# GC-Sch.net
KiCad netlist of a schematic drawn in Altium Designer
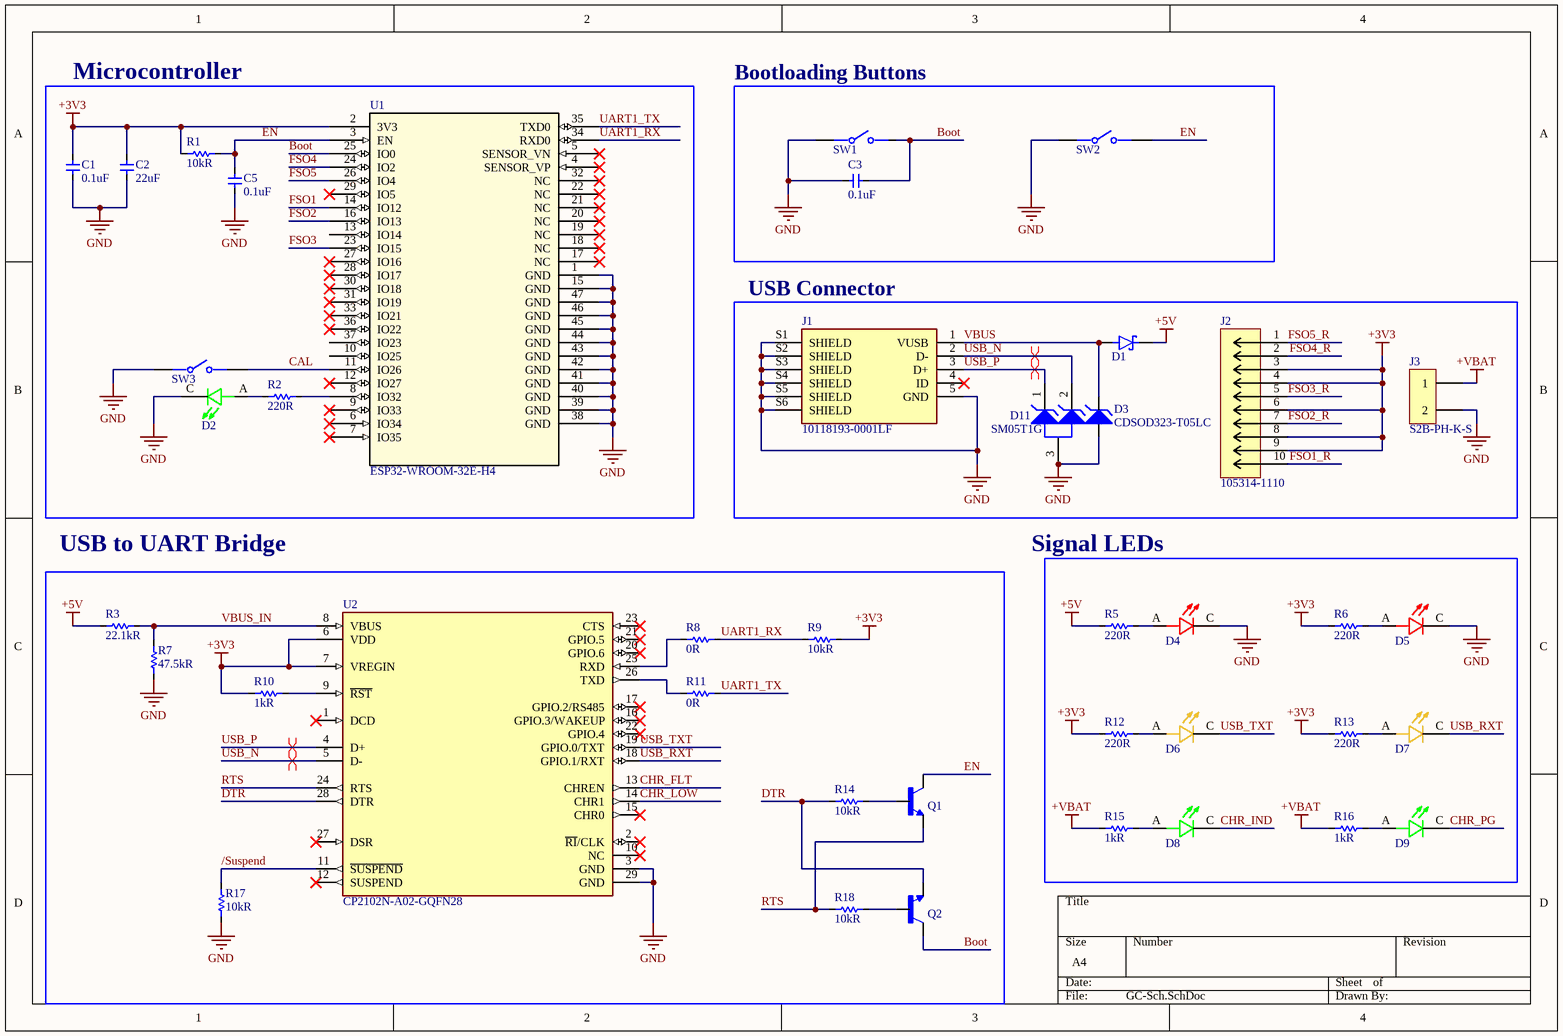
[diagram p0: GC-Sch.SchDoc]

(export (version "E")
  (design (tool "Eeschema 10.0.6"))
  (components
    (comp (ref "C1")
      (value "CL10B104JB8NNNC")
      (footprint "0603")
      (fields (field (name "MANUFACTURER") "Samsung") (field (name "CAPACITANCE") "0.1uF"))
      (libsource (lib "GC-Schlib1") (part "CL10B104JB8NNNC"))
    )
    (comp (ref "C2")
      (value "CL10A226MP8NUNE")
      (footprint "0603")
      (fields (field (name "MANUFACTURER") "Samsung") (field (name "CAPACITANCE") "22uF"))
      (libsource (lib "GC-Schlib1") (part "CL10A226MP8NUNE"))
    )
    (comp (ref "C3")
      (value "CL10B104JB8NNNC")
      (footprint "0603")
      (fields (field (name "MANUFACTURER") "Samsung") (field (name "CAPACITANCE") "0.1uF"))
      (libsource (lib "GC-Schlib1") (part "C-CL10B104JB8NNNC"))
    )
    (comp (ref "C5")
      (value "CL10B104JB8NNNC")
      (footprint "0603")
      (fields (field (name "MANUFACTURER") "Samsung") (field (name "CAPACITANCE") "0.1uF"))
      (libsource (lib "GC-Schlib1") (part "CL10B104JB8NNNC"))
    )
    (comp (ref "D1")
      (value "D-BAT760-7")
      (footprint "SOD2513X120N")
      (description "Rectifier Diode, Schottky, 1 Phase, 1 Element, 1A, 30V V(RRM), Silicon")
      (fields (field (name "MANUFACTURER") "Diodes") (field (name "MANUFACTURER PART NUMBER") "BAT760-7"))
      (libsource (lib "GC-Schlib1") (part "D-BAT760-7"))
    )
    (comp (ref "D2")
      (value "SML-D12P8WT86")
      (footprint "D-SML-D12U1WT86")
      (description "Single Color LED, Pure Green, Diffused Milky White, 1.2mm")
      (fields (field (name "MANUFACTURER") "Rohm"))
      (libsource (lib "GC-Schlib1") (part "D-SML-D12P8WT86"))
    )
    (comp (ref "D3")
      (value "CDSOD323-T05LC")
      (footprint "SOD2513X120N")
      (description "Trans Voltage Suppressor Diode, 250W, 5V V(RWM), Bidirectional, 2 Element, Silicon")
      (fields (field (name "MANUFACTURER") "Bourns"))
      (libsource (lib "GC-Schlib1") (part "D-CDSOD323-T05LC"))
    )
    (comp (ref "D4")
      (value "SML-D12U1WT86")
      (footprint "D-SML-D12U1WT86")
      (description "Single Color LED, Red, Milky White, 1.2mm")
      (fields (field (name "MANUFACTURER") "Rohm"))
      (libsource (lib "GC-Schlib1") (part "D-SML-D12U1WT86"))
    )
    (comp (ref "D5")
      (value "SML-D12U1WT86")
      (footprint "D-SML-D12U1WT86")
      (description "Single Color LED, Red, Milky White, 1.2mm")
      (fields (field (name "MANUFACTURER") "Rohm"))
      (libsource (lib "GC-Schlib1") (part "D-SML-D12U1WT86"))
    )
    (comp (ref "D6")
      (value "SML-D12Y1WT86")
      (footprint "D-SML-D12U1WT86")
      (description "Single Color LED, Yellow, Milky White, 1.2mm")
      (fields (field (name "MANUFACTURER") "Rohm"))
      (libsource (lib "GC-Schlib1") (part "D-SML-D12Y1WT86"))
    )
    (comp (ref "D7")
      (value "SML-D12Y1WT86")
      (footprint "D-SML-D12U1WT86")
      (description "Single Color LED, Yellow, Milky White, 1.2mm")
      (fields (field (name "MANUFACTURER") "Rohm"))
      (libsource (lib "GC-Schlib1") (part "D-SML-D12Y1WT86"))
    )
    (comp (ref "D8")
      (value "SML-D12P8WT86")
      (footprint "D-SML-D12U1WT86")
      (description "Single Color LED, Pure Green, Diffused Milky White, 1.2mm")
      (fields (field (name "MANUFACTURER") "Rohm"))
      (libsource (lib "GC-Schlib1") (part "D-SML-D12P8WT86"))
    )
    (comp (ref "D9")
      (value "SML-D12P8WT86")
      (footprint "D-SML-D12U1WT86")
      (description "Single Color LED, Pure Green, Diffused Milky White, 1.2mm")
      (fields (field (name "MANUFACTURER") "Rohm"))
      (libsource (lib "GC-Schlib1") (part "D-SML-D12P8WT86"))
    )
    (comp (ref "D11")
      (value "SM05T1G")
      (footprint "ONSC-SOT-23-3-318-08_V")
      (description "Trans Voltage Suppressor Diode, 300W, 5V V(RWM), Unidirectional, 2 Element, Silicon, TO-236AB")
      (fields (field (name "MANUFACTURER") "ON Semiconductor"))
      (libsource (lib "GC-Schlib1") (part "D-SM05T1G"))
    )
    (comp (ref "J1")
      (value "10118193-0001LF")
      (footprint "AMPHENOL_10118193-0001LF")
      (description "FCI Right Angle Surface Mount Mount Female USB Connector; 100 V ac; 1.8A")
      (fields (field (name "MANUFACTURER") "Amphenol ICC / FCI"))
      (libsource (lib "GC-Schlib1") (part "J-10118193-0001LF"))
    )
    (comp (ref "J2")
      (value "105314-1110")
      (footprint "temp")
      (description "Rectangular Power Connector, 10 Contact(s), Male, Solder Terminal")
      (fields (field (name "MANUFACTURER") "Molex"))
      (libsource (lib "GC-Schlib1") (part "J-105314-1110"))
    )
    (comp (ref "J3")
      (value "S2B-PH-K-S")
      (footprint "JST_S2B-PH-K-S(LF)(SN)")
      (description "Header for PCB; pitch 2.00mm; 2-contacts; THT; male; side entry; 100V/2A")
      (fields
        (field (name "MANUFACTURER") "JST")
        (field (name "MANUFACTURER PART NUMBER") "S2B-PH-K-S(LF)(SN)")
      )
      (libsource (lib "GC-Schlib1") (part "J-S2B-PH-K-S(LF)(SN)"))
    )
    (comp (ref "Q1")
      (value "SS8050-G")
      (footprint "TRANS_SS8050-G")
      (description "Small Signal Bipolar Transistor, 1.5A I(C), 25V V(BR)CEO, 1-Element, NPN, Silicon")
      (fields (field (name "MANUFACTURER") "Comchip"))
      (libsource (lib "") (part "Q-SS8050-G_1"))
    )
    (comp (ref "Q2")
      (value "SS8050-G")
      (footprint "TRANS_SS8050-G")
      (description "Small Signal Bipolar Transistor, 1.5A I(C), 25V V(BR)CEO, 1-Element, NPN, Silicon")
      (fields (field (name "MANUFACTURER") "Comchip"))
      (libsource (lib "GC-Schlib1") (part "Q-SS8050-G"))
    )
    (comp (ref "R1")
      (value "AC0603FR-1310KL")
      (footprint "0603 - R")
      (fields
        (field (name "MANUFACTURER") "Yageo")
        (field (name "TOLERANCE") "1%")
        (field (name "RESISTANCE") "10kR")
      )
      (libsource (lib "GC-Schlib1") (part "AC0603FR-1310KL"))
    )
    (comp (ref "R2")
      (value "R-RMCF0603JT220R")
      (footprint "0603 - R")
      (fields
        (field (name "MANUFACTURER") "Stackpole Electronics")
        (field (name "MANUFACTURER PART NUMBER") "RMCF0603JT220R")
        (field (name "TOLERANCE") "5%")
        (field (name "RESISTANCE") "220R")
      )
      (libsource (lib "GC-Schlib1") (part "R-RMCF0603JT220R"))
    )
    (comp (ref "R3")
      (value "RMCF0603FT22K1")
      (footprint "0603 - R")
      (fields
        (field (name "MANUFACTURER") "Stackpole Electronics")
        (field (name "TOLERANCE") "1%")
        (field (name "RESISTANCE") "22.1kR")
      )
      (libsource (lib "GC-Schlib1") (part "R-RMCF0603FT22K1"))
    )
    (comp (ref "R5")
      (value "R-RMCF0603JT220R")
      (footprint "0603 - R")
      (fields
        (field (name "MANUFACTURER") "Stackpole Electronics")
        (field (name "MANUFACTURER PART NUMBER") "RMCF0603JT220R")
        (field (name "TOLERANCE") "5%")
        (field (name "RESISTANCE") "220R")
      )
      (libsource (lib "GC-Schlib1") (part "R-RMCF0603JT220R"))
    )
    (comp (ref "R6")
      (value "R-RMCF0603JT220R")
      (footprint "0603 - R")
      (fields
        (field (name "MANUFACTURER") "Stackpole Electronics")
        (field (name "MANUFACTURER PART NUMBER") "RMCF0603JT220R")
        (field (name "TOLERANCE") "5%")
        (field (name "RESISTANCE") "220R")
      )
      (libsource (lib "GC-Schlib1") (part "R-RMCF0603JT220R"))
    )
    (comp (ref "R7")
      (value "RC0402FR-0747K5L")
      (footprint "0603 - R")
      (fields
        (field (name "MANUFACTURER") "Yageo")
        (field (name "TOLERANCE") "1%")
        (field (name "RESISTANCE") "47.5kR")
      )
      (libsource (lib "GC-Schlib1") (part "R-RC0402FR-0747K5L"))
    )
    (comp (ref "R8")
      (value "ERJ-3GEY0R00V")
      (footprint "0603 - R")
      (description "Fixed Resistor, Metal Glaze/thick Film, 0.1W, 0ohm, Surface Mount, 0603")
      (fields (field (name "MANUFACTURER") "Panasonic") (field (name "RESISTANCE") "0R"))
      (libsource (lib "GC-Schlib1") (part "R-ERJ-3GEY0R00V"))
    )
    (comp (ref "R9")
      (value "AC0603FR-1310KL")
      (footprint "0603 - R")
      (fields
        (field (name "MANUFACTURER") "Yageo")
        (field (name "TOLERANCE") "1%")
        (field (name "RESISTANCE") "10kR")
      )
      (libsource (lib "GC-Schlib1") (part "R-AC0603FR-1310KL"))
    )
    (comp (ref "R10")
      (value "RC0603FR-071KL")
      (footprint "0603 - R")
      (fields
        (field (name "MANUFACTURER") "Yageo")
        (field (name "TOLERANCE") "1%")
        (field (name "RESISTANCE") "1kR")
      )
      (libsource (lib "GC-Schlib1") (part "R-RC0603FR-071KL"))
    )
    (comp (ref "R11")
      (value "ERJ-3GEY0R00V")
      (footprint "0603 - R")
      (description "Fixed Resistor, Metal Glaze/thick Film, 0.1W, 0ohm, Surface Mount, 0603")
      (fields (field (name "MANUFACTURER") "Panasonic") (field (name "RESISTANCE") "0R"))
      (libsource (lib "GC-Schlib1") (part "R-ERJ-3GEY0R00V"))
    )
    (comp (ref "R12")
      (value "R-RMCF0603JT220R")
      (footprint "0603 - R")
      (fields
        (field (name "MANUFACTURER") "Stackpole Electronics")
        (field (name "MANUFACTURER PART NUMBER") "RMCF0603JT220R")
        (field (name "TOLERANCE") "5%")
        (field (name "RESISTANCE") "220R")
      )
      (libsource (lib "GC-Schlib1") (part "R-RMCF0603JT220R"))
    )
    (comp (ref "R13")
      (value "R-RMCF0603JT220R")
      (footprint "0603 - R")
      (fields
        (field (name "MANUFACTURER") "Stackpole Electronics")
        (field (name "MANUFACTURER PART NUMBER") "RMCF0603JT220R")
        (field (name "TOLERANCE") "5%")
        (field (name "RESISTANCE") "220R")
      )
      (libsource (lib "GC-Schlib1") (part "R-RMCF0603JT220R"))
    )
    (comp (ref "R14")
      (value "AC0603FR-1310KL")
      (footprint "0603 - R")
      (fields
        (field (name "MANUFACTURER") "Yageo")
        (field (name "TOLERANCE") "1%")
        (field (name "RESISTANCE") "10kR")
      )
      (libsource (lib "GC-Schlib1") (part "R-AC0603FR-1310KL"))
    )
    (comp (ref "R15")
      (value "RC0603FR-071KL")
      (footprint "0603 - R")
      (fields
        (field (name "MANUFACTURER") "Yageo")
        (field (name "TOLERANCE") "1%")
        (field (name "RESISTANCE") "1kR")
      )
      (libsource (lib "GC-Schlib1") (part "R-RC0603FR-071KL"))
    )
    (comp (ref "R16")
      (value "RC0603FR-071KL")
      (footprint "0603 - R")
      (fields
        (field (name "MANUFACTURER") "Yageo")
        (field (name "TOLERANCE") "1%")
        (field (name "RESISTANCE") "1kR")
      )
      (libsource (lib "GC-Schlib1") (part "R-RC0603FR-071KL"))
    )
    (comp (ref "R17")
      (value "AC0603FR-1310KL")
      (footprint "0603 - R")
      (fields
        (field (name "MANUFACTURER") "Yageo")
        (field (name "TOLERANCE") "1%")
        (field (name "RESISTANCE") "10kR")
      )
      (libsource (lib "GC-Schlib1") (part "R-AC0603FR-1310KL"))
    )
    (comp (ref "R18")
      (value "AC0603FR-1310KL")
      (footprint "0603 - R")
      (fields
        (field (name "MANUFACTURER") "Yageo")
        (field (name "TOLERANCE") "1%")
        (field (name "RESISTANCE") "10kR")
      )
      (libsource (lib "GC-Schlib1") (part "R-AC0603FR-1310KL"))
    )
    (comp (ref "SW1")
      (value "SW-61300211121")
      (footprint "2 Pin Through Hole - Pitch 2.54 mm")
      (fields
        (field (name "MANUFACTURER") "Wurth Electronics")
        (field (name "MANUFACTURER PART NUMBER") "61300211121")
      )
      (libsource (lib "GC-Schlib1") (part "SW-61300211121"))
    )
    (comp (ref "SW2")
      (value "SW-61300211121")
      (footprint "2 Pin Through Hole - Pitch 2.54 mm")
      (fields
        (field (name "MANUFACTURER") "Wurth Electronics")
        (field (name "MANUFACTURER PART NUMBER") "61300211121")
      )
      (libsource (lib "GC-Schlib1") (part "SW-61300211121"))
    )
    (comp (ref "SW3")
      (value "SW-61300211121")
      (footprint "2 Pin Through Hole - Pitch 2.54 mm")
      (fields
        (field (name "MANUFACTURER") "Wurth Electronics")
        (field (name "MANUFACTURER PART NUMBER") "61300211121")
      )
      (libsource (lib "GC-Schlib1") (part "SW-61300211121"))
    )
    (comp (ref "U1")
      (value "ESP32-WROOM-32E-H4")
      (footprint "ESP32­WROOM­32E_EXP")
      (description "Rx Txrx Mod Wifi Trace Ant SMD")
      (fields (field (name "MANUFACTURER") "Espressif Systems"))
      (libsource (lib "GC-Schlib1") (part "ESP32-WROOM-32E-H4"))
    )
    (comp (ref "U2")
      (value "CP2102N-A02-GQFN28")
      (footprint "FP-CP2102N-A02-GQFN28-IPC_A")
      (description "USB Bus Controller, CMOS")
      (fields (field (name "MANUFACTURER") "Silicon Labs"))
      (libsource (lib "GC-Schlib1") (part "U-CP2102N-A02-GQFN28"))
    )
  )
  (nets
    (net (code "1") (name "+3V3") (class "Default")
      (node (ref "C1") (pin "2") (pinfunction "2_2") (pintype "passive"))
      (node (ref "C2") (pin "1") (pinfunction "1_1") (pintype "passive"))
      (node (ref "J2") (pin "3") (pinfunction "3_3") (pintype "passive"))
      (node (ref "J2") (pin "4") (pinfunction "4_4") (pintype "passive"))
      (node (ref "J2") (pin "6") (pinfunction "6_6") (pintype "passive"))
      (node (ref "J2") (pin "8") (pinfunction "8_8") (pintype "passive"))
      (node (ref "J2") (pin "9") (pinfunction "9_9") (pintype "passive"))
      (node (ref "R1") (pin "1") (pinfunction "1_1") (pintype "passive"))
      (node (ref "R10") (pin "1") (pinfunction "1_1") (pintype "passive"))
      (node (ref "R12") (pin "1") (pinfunction "1_1") (pintype "passive"))
      (node (ref "R13") (pin "1") (pinfunction "1_1") (pintype "passive"))
      (node (ref "R6") (pin "1") (pinfunction "1_1") (pintype "passive"))
      (node (ref "R9") (pin "2") (pinfunction "2_2") (pintype "passive"))
      (node (ref "U1") (pin "2") (pinfunction "3V3_2") (pintype "power_in"))
      (node (ref "U2") (pin "6") (pinfunction "VDD_6") (pintype "power_in"))
      (node (ref "U2") (pin "7") (pinfunction "VREGIN_7") (pintype "input"))
    )
    (net (code "2") (name "+5V") (class "Default")
      (node (ref "D1") (pin "C") (pinfunction "K_C") (pintype "passive"))
      (node (ref "R3") (pin "1") (pinfunction "1_1") (pintype "passive"))
      (node (ref "R5") (pin "1") (pinfunction "1_1") (pintype "passive"))
    )
    (net (code "3") (name "+VBAT") (class "Default")
      (node (ref "J3") (pin "1") (pinfunction "1_1") (pintype "passive"))
      (node (ref "R15") (pin "1") (pinfunction "1_1") (pintype "passive"))
      (node (ref "R16") (pin "1") (pinfunction "1_1") (pintype "passive"))
    )
    (net (code "4") (name "/Boot") (class "Default")
      (node (ref "C3") (pin "1") (pinfunction "1_1") (pintype "passive"))
      (node (ref "Q2") (pin "3") (pinfunction "C_3") (pintype "passive"))
      (node (ref "SW1") (pin "2") (pinfunction "2_2") (pintype "passive"))
      (node (ref "U1") (pin "25") (pinfunction "IO0_25") (pintype "bidirectional"))
    )
    (net (code "5") (name "/CAL") (class "Default")
      (node (ref "SW3") (pin "2") (pinfunction "2_2") (pintype "passive"))
      (node (ref "U1") (pin "11") (pinfunction "IO26_11") (pintype "bidirectional"))
    )
    (net (code "6") (name "/CHR_FLT") (class "Default")
      (node (ref "U2") (pin "13") (pinfunction "CHREN_13") (pintype "output"))
    )
    (net (code "7") (name "/CHR_IND") (class "Default")
      (node (ref "D8") (pin "C") (pinfunction "C_C") (pintype "passive"))
    )
    (net (code "8") (name "/CHR_LOW") (class "Default")
      (node (ref "U2") (pin "14") (pinfunction "CHR1_14") (pintype "output"))
    )
    (net (code "9") (name "/CHR_PG") (class "Default")
      (node (ref "D9") (pin "C") (pinfunction "C_C") (pintype "passive"))
    )
    (net (code "10") (name "/DTR") (class "Default")
      (node (ref "Q2") (pin "2") (pinfunction "E_2") (pintype "passive"))
      (node (ref "R14") (pin "1") (pinfunction "1_1") (pintype "passive"))
      (node (ref "U2") (pin "28") (pinfunction "DTR_28") (pintype "output"))
    )
    (net (code "11") (name "/EN") (class "Default")
      (node (ref "C5") (pin "2") (pinfunction "2_2") (pintype "passive"))
      (node (ref "Q1") (pin "3") (pinfunction "C_3") (pintype "passive"))
      (node (ref "R1") (pin "2") (pinfunction "2_2") (pintype "passive"))
      (node (ref "SW2") (pin "2") (pinfunction "2_2") (pintype "passive"))
      (node (ref "U1") (pin "3") (pinfunction "EN_3") (pintype "input"))
    )
    (net (code "12") (name "/FSO1") (class "Default")
      (node (ref "U1") (pin "14") (pinfunction "IO12_14") (pintype "bidirectional"))
    )
    (net (code "13") (name "/FSO1_R") (class "Default")
      (node (ref "J2") (pin "10") (pinfunction "10_10") (pintype "passive"))
    )
    (net (code "14") (name "/FSO2") (class "Default")
      (node (ref "U1") (pin "16") (pinfunction "IO13_16") (pintype "bidirectional"))
    )
    (net (code "15") (name "/FSO2_R") (class "Default")
      (node (ref "J2") (pin "7") (pinfunction "7_7") (pintype "passive"))
    )
    (net (code "16") (name "/FSO3") (class "Default")
      (node (ref "U1") (pin "23") (pinfunction "IO15_23") (pintype "bidirectional"))
    )
    (net (code "17") (name "/FSO3_R") (class "Default")
      (node (ref "J2") (pin "5") (pinfunction "5_5") (pintype "passive"))
    )
    (net (code "18") (name "/FSO4") (class "Default")
      (node (ref "U1") (pin "24") (pinfunction "IO2_24") (pintype "bidirectional"))
    )
    (net (code "19") (name "/FSO4_R") (class "Default")
      (node (ref "J2") (pin "2") (pinfunction "2_2") (pintype "passive"))
    )
    (net (code "20") (name "/FSO5") (class "Default")
      (node (ref "U1") (pin "26") (pinfunction "IO4_26") (pintype "bidirectional"))
    )
    (net (code "21") (name "/FSO5_R") (class "Default")
      (node (ref "J2") (pin "1") (pinfunction "1_1") (pintype "passive"))
    )
    (net (code "22") (name "/RTS") (class "Default")
      (node (ref "Q1") (pin "2") (pinfunction "E_2") (pintype "passive"))
      (node (ref "R18") (pin "1") (pinfunction "1_1") (pintype "passive"))
      (node (ref "U2") (pin "24") (pinfunction "RTS_24") (pintype "output"))
    )
    (net (code "23") (name "/UART1_RX") (class "Default")
      (node (ref "R8") (pin "2") (pinfunction "2_2") (pintype "passive"))
      (node (ref "R9") (pin "1") (pinfunction "1_1") (pintype "passive"))
      (node (ref "U1") (pin "34") (pinfunction "RXD0_34") (pintype "bidirectional"))
    )
    (net (code "24") (name "/UART1_TX") (class "Default")
      (node (ref "R11") (pin "2") (pinfunction "2_2") (pintype "passive"))
      (node (ref "U1") (pin "35") (pinfunction "TXD0_35") (pintype "bidirectional"))
    )
    (net (code "25") (name "/USB_N") (class "Default")
      (node (ref "D11") (pin "2") (pinfunction "K2_2") (pintype "passive"))
      (node (ref "J1") (pin "2") (pinfunction "D-_2") (pintype "passive"))
      (node (ref "U2") (pin "5") (pinfunction "D-_5") (pintype "passive"))
    )
    (net (code "26") (name "/USB_P") (class "Default")
      (node (ref "D11") (pin "1") (pinfunction "K1_1") (pintype "passive"))
      (node (ref "J1") (pin "3") (pinfunction "D+_3") (pintype "passive"))
      (node (ref "U2") (pin "4") (pinfunction "D+_4") (pintype "passive"))
    )
    (net (code "27") (name "/USB_RXT") (class "Default")
      (node (ref "D7") (pin "C") (pinfunction "C_C") (pintype "passive"))
      (node (ref "U2") (pin "18") (pinfunction "GPIO.1/RXT_18") (pintype "bidirectional"))
    )
    (net (code "28") (name "/USB_TXT") (class "Default")
      (node (ref "D6") (pin "C") (pinfunction "C_C") (pintype "passive"))
      (node (ref "U2") (pin "19") (pinfunction "GPIO.0/TXT_19") (pintype "bidirectional"))
    )
    (net (code "29") (name "/VBUS") (class "Default")
      (node (ref "D1") (pin "A") (pinfunction "A_A") (pintype "passive"))
      (node (ref "D3") (pin "C") (pinfunction "C_C") (pintype "passive"))
      (node (ref "J1") (pin "1") (pinfunction "VUSB_1") (pintype "passive"))
    )
    (net (code "30") (name "/VBUS_IN") (class "Default")
      (node (ref "R3") (pin "2") (pinfunction "2_2") (pintype "passive"))
      (node (ref "R7") (pin "2") (pinfunction "2_2") (pintype "passive"))
      (node (ref "U2") (pin "8") (pinfunction "VBUS_8") (pintype "input"))
    )
    (net (code "31") (name "/{slash}Suspend") (class "Default")
      (node (ref "R17") (pin "2") (pinfunction "2_2") (pintype "passive"))
      (node (ref "U2") (pin "11") (pinfunction "~{SUSPEND}_11") (pintype "output"))
    )
    (net (code "32") (name "GND") (class "Default")
      (node (ref "C1") (pin "1") (pinfunction "1_1") (pintype "passive"))
      (node (ref "C2") (pin "2") (pinfunction "2_2") (pintype "passive"))
      (node (ref "C3") (pin "2") (pinfunction "2_2") (pintype "passive"))
      (node (ref "C5") (pin "1") (pinfunction "1_1") (pintype "passive"))
      (node (ref "D11") (pin "3") (pinfunction "A_3") (pintype "passive"))
      (node (ref "D2") (pin "C") (pinfunction "C_C") (pintype "passive"))
      (node (ref "D3") (pin "A") (pinfunction "A_A") (pintype "passive"))
      (node (ref "D4") (pin "C") (pinfunction "C_C") (pintype "passive"))
      (node (ref "D5") (pin "C") (pinfunction "C_C") (pintype "passive"))
      (node (ref "J1") (pin "5") (pinfunction "GND_5") (pintype "passive"))
      (node (ref "J1") (pin "S1") (pinfunction "SHIELD_S1") (pintype "passive"))
      (node (ref "J1") (pin "S2") (pinfunction "SHIELD_S2") (pintype "passive"))
      (node (ref "J1") (pin "S3") (pinfunction "SHIELD_S3") (pintype "passive"))
      (node (ref "J1") (pin "S4") (pinfunction "SHIELD_S4") (pintype "passive"))
      (node (ref "J1") (pin "S5") (pinfunction "SHIELD_S5") (pintype "passive"))
      (node (ref "J1") (pin "S6") (pinfunction "SHIELD_S6") (pintype "passive"))
      (node (ref "J3") (pin "2") (pinfunction "2_2") (pintype "passive"))
      (node (ref "R17") (pin "1") (pinfunction "1_1") (pintype "passive"))
      (node (ref "R7") (pin "1") (pinfunction "1_1") (pintype "passive"))
      (node (ref "SW1") (pin "1") (pinfunction "1_1") (pintype "passive"))
      (node (ref "SW2") (pin "1") (pinfunction "1_1") (pintype "passive"))
      (node (ref "SW3") (pin "1") (pinfunction "1_1") (pintype "passive"))
      (node (ref "U1") (pin "1") (pinfunction "GND_1") (pintype "power_in"))
      (node (ref "U1") (pin "15") (pinfunction "GND_15") (pintype "power_in"))
      (node (ref "U1") (pin "38") (pinfunction "GND_38") (pintype "power_in"))
      (node (ref "U1") (pin "39") (pinfunction "GND_39") (pintype "power_in"))
      (node (ref "U1") (pin "40") (pinfunction "GND_40") (pintype "power_in"))
      (node (ref "U1") (pin "41") (pinfunction "GND_41") (pintype "power_in"))
      (node (ref "U1") (pin "42") (pinfunction "GND_42") (pintype "power_in"))
      (node (ref "U1") (pin "43") (pinfunction "GND_43") (pintype "power_in"))
      (node (ref "U1") (pin "44") (pinfunction "GND_44") (pintype "power_in"))
      (node (ref "U1") (pin "45") (pinfunction "GND_45") (pintype "power_in"))
      (node (ref "U1") (pin "46") (pinfunction "GND_46") (pintype "power_in"))
      (node (ref "U1") (pin "47") (pinfunction "GND_47") (pintype "power_in"))
      (node (ref "U2") (pin "29") (pinfunction "GND_29") (pintype "power_in"))
      (node (ref "U2") (pin "3") (pinfunction "GND_3") (pintype "power_in"))
    )
    (net (code "33") (name "Net-(D2-PadA)") (class "Default")
      (node (ref "D2") (pin "A") (pinfunction "A_A") (pintype "passive"))
      (node (ref "R2") (pin "2") (pinfunction "2_2") (pintype "passive"))
    )
    (net (code "34") (name "Net-(D4-PadA)") (class "Default")
      (node (ref "D4") (pin "A") (pinfunction "A_A") (pintype "passive"))
      (node (ref "R5") (pin "2") (pinfunction "2_2") (pintype "passive"))
    )
    (net (code "35") (name "Net-(D5-PadA)") (class "Default")
      (node (ref "D5") (pin "A") (pinfunction "A_A") (pintype "passive"))
      (node (ref "R6") (pin "2") (pinfunction "2_2") (pintype "passive"))
    )
    (net (code "36") (name "Net-(D6-PadA)") (class "Default")
      (node (ref "D6") (pin "A") (pinfunction "A_A") (pintype "passive"))
      (node (ref "R12") (pin "2") (pinfunction "2_2") (pintype "passive"))
    )
    (net (code "37") (name "Net-(D7-PadA)") (class "Default")
      (node (ref "D7") (pin "A") (pinfunction "A_A") (pintype "passive"))
      (node (ref "R13") (pin "2") (pinfunction "2_2") (pintype "passive"))
    )
    (net (code "38") (name "Net-(D8-PadA)") (class "Default")
      (node (ref "D8") (pin "A") (pinfunction "A_A") (pintype "passive"))
      (node (ref "R15") (pin "2") (pinfunction "2_2") (pintype "passive"))
    )
    (net (code "39") (name "Net-(D9-PadA)") (class "Default")
      (node (ref "D9") (pin "A") (pinfunction "A_A") (pintype "passive"))
      (node (ref "R16") (pin "2") (pinfunction "2_2") (pintype "passive"))
    )
    (net (code "40") (name "Net-(Q1-B)") (class "Default")
      (node (ref "Q1") (pin "1") (pinfunction "B_1") (pintype "passive"))
      (node (ref "R14") (pin "2") (pinfunction "2_2") (pintype "passive"))
    )
    (net (code "41") (name "Net-(Q2-B)") (class "Default")
      (node (ref "Q2") (pin "1") (pinfunction "B_1") (pintype "passive"))
      (node (ref "R18") (pin "2") (pinfunction "2_2") (pintype "passive"))
    )
    (net (code "42") (name "Net-(U1-IO32)") (class "Default")
      (node (ref "R2") (pin "1") (pinfunction "1_1") (pintype "passive"))
      (node (ref "U1") (pin "8") (pinfunction "IO32_8") (pintype "bidirectional"))
    )
    (net (code "43") (name "Net-(U2-RXD)") (class "Default")
      (node (ref "R8") (pin "1") (pinfunction "1_1") (pintype "passive"))
      (node (ref "U2") (pin "25") (pinfunction "RXD_25") (pintype "input"))
    )
    (net (code "44") (name "Net-(U2-TXD)") (class "Default")
      (node (ref "R11") (pin "1") (pinfunction "1_1") (pintype "passive"))
      (node (ref "U2") (pin "26") (pinfunction "TXD_26") (pintype "output"))
    )
    (net (code "45") (name "Net-(U2-~{RST})") (class "Default")
      (node (ref "R10") (pin "2") (pinfunction "2_2") (pintype "passive"))
      (node (ref "U2") (pin "9") (pinfunction "~{RST}_9") (pintype "input"))
    )
    (net (code "46") (name "unconnected-(J1-ID-Pad4)") (class "Default")
      (node (ref "J1") (pin "4") (pinfunction "ID_4") (pintype "passive+no_connect"))
    )
    (net (code "47") (name "unconnected-(U1-IO5-Pad29)") (class "Default")
      (node (ref "U1") (pin "29") (pinfunction "IO5_29") (pintype "bidirectional+no_connect"))
    )
    (net (code "48") (name "unconnected-(U1-IO14-Pad13)") (class "Default")
      (node (ref "U1") (pin "13") (pinfunction "IO14_13") (pintype "bidirectional"))
    )
    (net (code "49") (name "unconnected-(U1-IO16-Pad27)") (class "Default")
      (node (ref "U1") (pin "27") (pinfunction "IO16_27") (pintype "bidirectional+no_connect"))
    )
    (net (code "50") (name "unconnected-(U1-IO17-Pad28)") (class "Default")
      (node (ref "U1") (pin "28") (pinfunction "IO17_28") (pintype "bidirectional+no_connect"))
    )
    (net (code "51") (name "unconnected-(U1-IO18-Pad30)") (class "Default")
      (node (ref "U1") (pin "30") (pinfunction "IO18_30") (pintype "bidirectional+no_connect"))
    )
    (net (code "52") (name "unconnected-(U1-IO19-Pad31)") (class "Default")
      (node (ref "U1") (pin "31") (pinfunction "IO19_31") (pintype "bidirectional+no_connect"))
    )
    (net (code "53") (name "unconnected-(U1-IO21-Pad33)") (class "Default")
      (node (ref "U1") (pin "33") (pinfunction "IO21_33") (pintype "bidirectional+no_connect"))
    )
    (net (code "54") (name "unconnected-(U1-IO22-Pad36)") (class "Default")
      (node (ref "U1") (pin "36") (pinfunction "IO22_36") (pintype "bidirectional+no_connect"))
    )
    (net (code "55") (name "unconnected-(U1-IO23-Pad37)") (class "Default")
      (node (ref "U1") (pin "37") (pinfunction "IO23_37") (pintype "bidirectional"))
    )
    (net (code "56") (name "unconnected-(U1-IO25-Pad10)") (class "Default")
      (node (ref "U1") (pin "10") (pinfunction "IO25_10") (pintype "bidirectional"))
    )
    (net (code "57") (name "unconnected-(U1-IO27-Pad12)") (class "Default")
      (node (ref "U1") (pin "12") (pinfunction "IO27_12") (pintype "bidirectional+no_connect"))
    )
    (net (code "58") (name "unconnected-(U1-IO33-Pad9)") (class "Default")
      (node (ref "U1") (pin "9") (pinfunction "IO33_9") (pintype "bidirectional+no_connect"))
    )
    (net (code "59") (name "unconnected-(U1-IO34-Pad6)") (class "Default")
      (node (ref "U1") (pin "6") (pinfunction "IO34_6") (pintype "input+no_connect"))
    )
    (net (code "60") (name "unconnected-(U1-IO35-Pad7)") (class "Default")
      (node (ref "U1") (pin "7") (pinfunction "IO35_7") (pintype "input+no_connect"))
    )
    (net (code "61") (name "unconnected-(U1-NC-Pad17)") (class "Default")
      (node (ref "U1") (pin "17") (pinfunction "NC_17") (pintype "passive+no_connect"))
    )
    (net (code "62") (name "unconnected-(U1-NC-Pad18)") (class "Default")
      (node (ref "U1") (pin "18") (pinfunction "NC_18") (pintype "passive+no_connect"))
    )
    (net (code "63") (name "unconnected-(U1-NC-Pad19)") (class "Default")
      (node (ref "U1") (pin "19") (pinfunction "NC_19") (pintype "passive+no_connect"))
    )
    (net (code "64") (name "unconnected-(U1-NC-Pad20)") (class "Default")
      (node (ref "U1") (pin "20") (pinfunction "NC_20") (pintype "passive+no_connect"))
    )
    (net (code "65") (name "unconnected-(U1-NC-Pad21)") (class "Default")
      (node (ref "U1") (pin "21") (pinfunction "NC_21") (pintype "passive+no_connect"))
    )
    (net (code "66") (name "unconnected-(U1-NC-Pad22)") (class "Default")
      (node (ref "U1") (pin "22") (pinfunction "NC_22") (pintype "passive+no_connect"))
    )
    (net (code "67") (name "unconnected-(U1-NC-Pad32)") (class "Default")
      (node (ref "U1") (pin "32") (pinfunction "NC_32") (pintype "passive+no_connect"))
    )
    (net (code "68") (name "unconnected-(U1-SENSOR_VN-Pad5)") (class "Default")
      (node (ref "U1") (pin "5") (pinfunction "SENSOR_VN_5") (pintype "input+no_connect"))
    )
    (net (code "69") (name "unconnected-(U1-SENSOR_VP-Pad4)") (class "Default")
      (node (ref "U1") (pin "4") (pinfunction "SENSOR_VP_4") (pintype "input+no_connect"))
    )
    (net (code "70") (name "unconnected-(U2-CHR0-Pad15)") (class "Default")
      (node (ref "U2") (pin "15") (pinfunction "CHR0_15") (pintype "output+no_connect"))
    )
    (net (code "71") (name "unconnected-(U2-CTS-Pad23)") (class "Default")
      (node (ref "U2") (pin "23") (pinfunction "CTS_23") (pintype "input+no_connect"))
    )
    (net (code "72") (name "unconnected-(U2-DCD-Pad1)") (class "Default")
      (node (ref "U2") (pin "1") (pinfunction "DCD_1") (pintype "input+no_connect"))
    )
    (net (code "73") (name "unconnected-(U2-DSR-Pad27)") (class "Default")
      (node (ref "U2") (pin "27") (pinfunction "DSR_27") (pintype "input+no_connect"))
    )
    (net (code "74") (name "unconnected-(U2-GPIO.2{slash}RS485-Pad17)") (class "Default")
      (node (ref "U2") (pin "17") (pinfunction "GPIO.2/RS485_17") (pintype "bidirectional+no_connect"))
    )
    (net (code "75") (name "unconnected-(U2-GPIO.3{slash}WAKEUP-Pad16)") (class "Default")
      (node (ref "U2") (pin "16") (pinfunction "GPIO.3/WAKEUP_16") (pintype "bidirectional+no_connect"))
    )
    (net (code "76") (name "unconnected-(U2-GPIO.4-Pad22)") (class "Default")
      (node (ref "U2") (pin "22") (pinfunction "GPIO.4_22") (pintype "bidirectional+no_connect"))
    )
    (net (code "77") (name "unconnected-(U2-GPIO.5-Pad21)") (class "Default")
      (node (ref "U2") (pin "21") (pinfunction "GPIO.5_21") (pintype "bidirectional+no_connect"))
    )
    (net (code "78") (name "unconnected-(U2-GPIO.6-Pad20)") (class "Default")
      (node (ref "U2") (pin "20") (pinfunction "GPIO.6_20") (pintype "bidirectional+no_connect"))
    )
    (net (code "79") (name "unconnected-(U2-NC-Pad10)") (class "Default")
      (node (ref "U2") (pin "10") (pinfunction "NC_10") (pintype "passive+no_connect"))
    )
    (net (code "80") (name "unconnected-(U2-SUSPEND-Pad12)") (class "Default")
      (node (ref "U2") (pin "12") (pinfunction "SUSPEND_12") (pintype "output+no_connect"))
    )
    (net (code "81") (name "unconnected-(U2-~{RI}{slash}CLK-Pad2)") (class "Default")
      (node (ref "U2") (pin "2") (pinfunction "~{RI}/CLK_2") (pintype "bidirectional+no_connect"))
    )
  )
)
